# 5411507.net
KiCad netlist of a schematic drawn in EAGLE
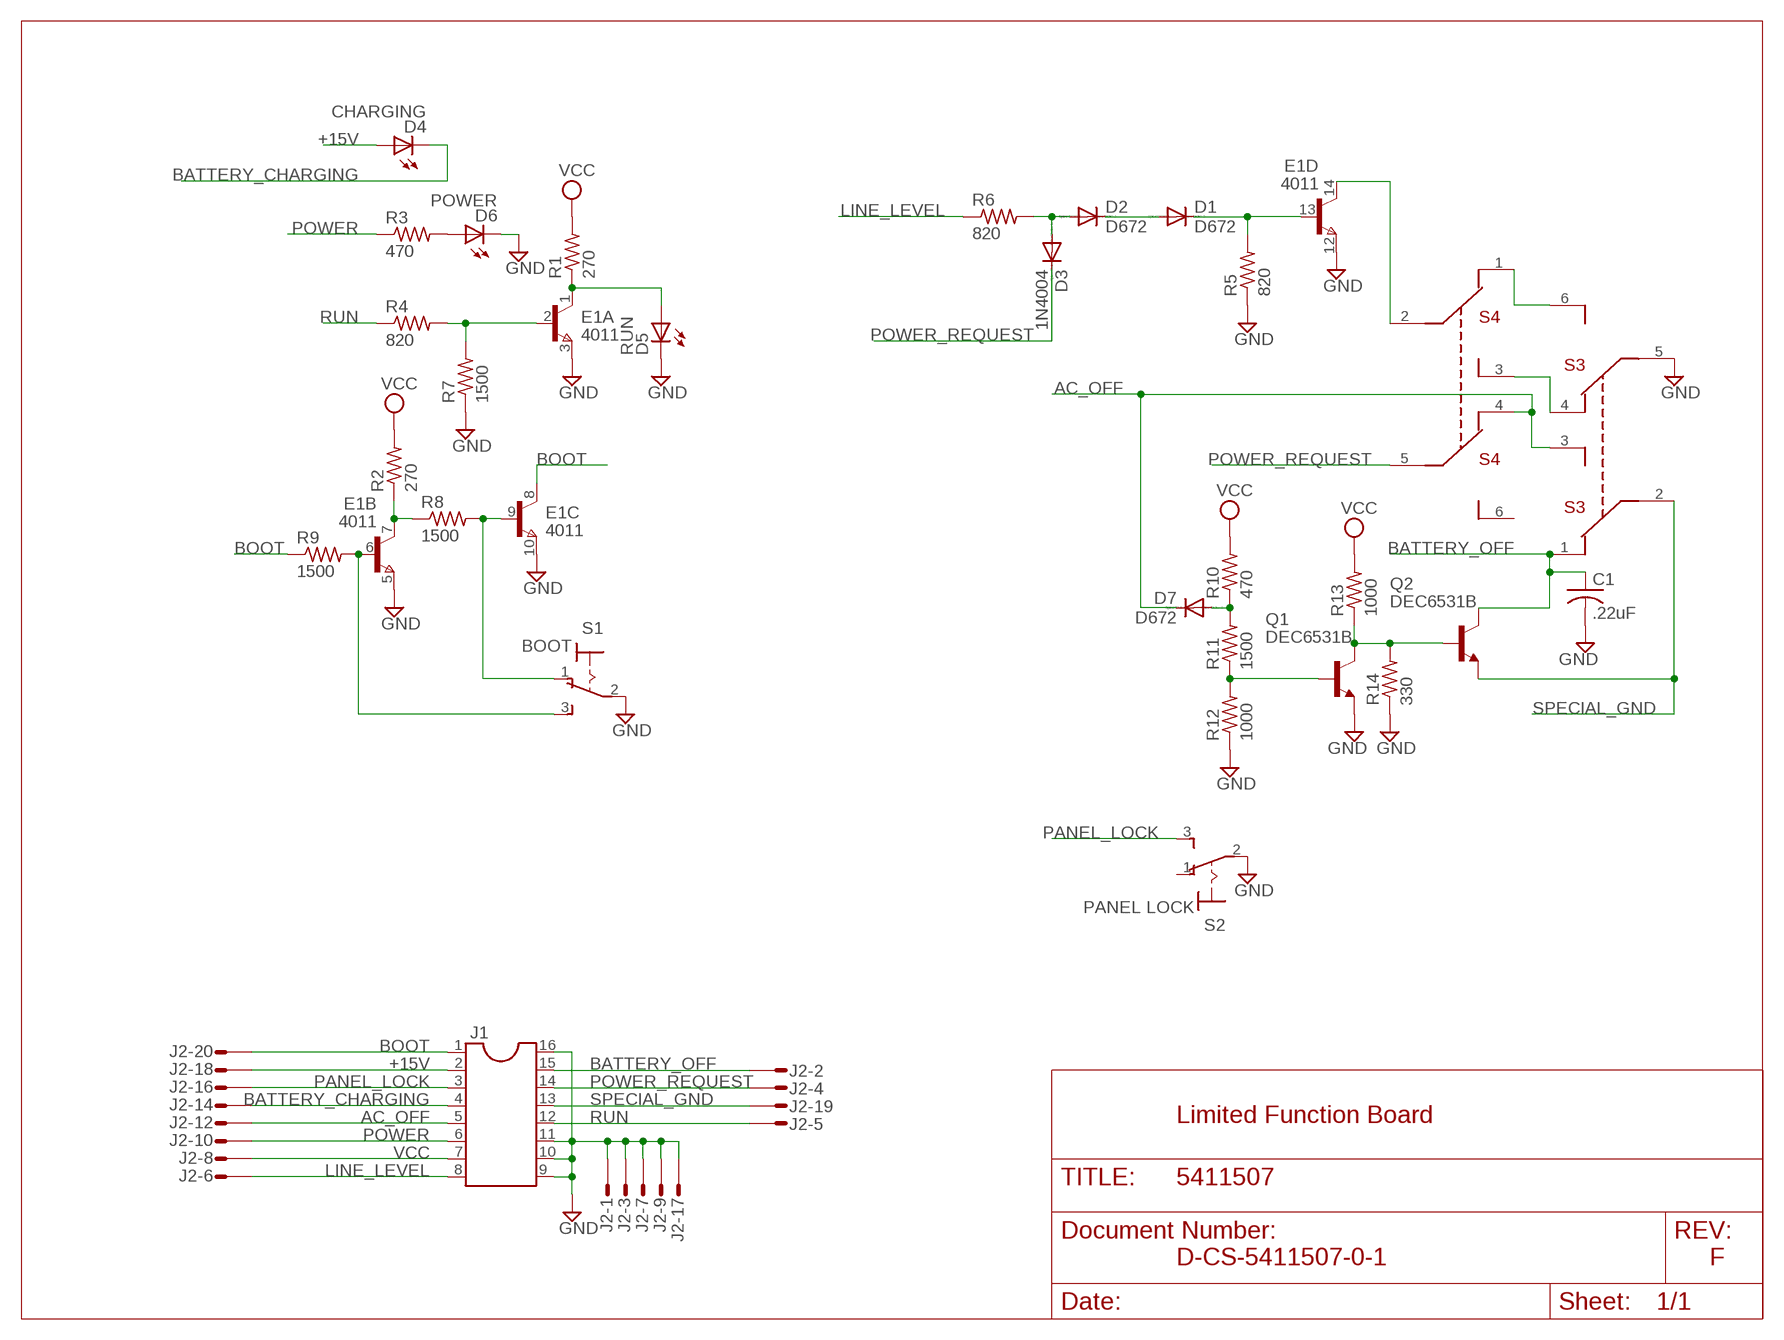
[diagram p0: schematic, sheet 1]

(export (version "E")
  (design (tool "Eeschema 10.0.6"))
  (components
    (comp (ref "C1")
      (value ".22uF")
      (footprint "eagle-import:C050-030X075")
      (libsource (lib "eagle-import") (part "C-US050-030X075"))
    )
    (comp (ref "D1")
      (value "D672")
      (footprint "eagle-import:DO35-10")
      (libsource (lib "eagle-import") (part "DIODE-DO35-10"))
    )
    (comp (ref "D2")
      (value "D672")
      (footprint "eagle-import:DO35-10")
      (libsource (lib "eagle-import") (part "DIODE-DO35-10"))
    )
    (comp (ref "D3")
      (value "1N4004")
      (footprint "eagle-import:DO41-10")
      (libsource (lib "eagle-import") (part "1N4004"))
    )
    (comp (ref "D4")
      (value "CHARGING")
      (footprint "eagle-import:LED5MM")
      (libsource (lib "eagle-import") (part "LED5MM"))
    )
    (comp (ref "D5")
      (value "RUN")
      (footprint "eagle-import:LED5MM")
      (libsource (lib "eagle-import") (part "LED5MM"))
    )
    (comp (ref "D6")
      (value "POWER")
      (footprint "eagle-import:LED5MM")
      (libsource (lib "eagle-import") (part "LED5MM"))
    )
    (comp (ref "D7")
      (value "D672")
      (footprint "eagle-import:DO35-10")
      (libsource (lib "eagle-import") (part "DIODE-DO35-10"))
    )
    (comp (ref "E1")
      (value "4011")
      (footprint "eagle-import:DIL14")
      (libsource (lib "eagle-import") (part "MAT-04Y"))
    )
    (comp (ref "J1")
      (value "DIL16S")
      (footprint "eagle-import:SOCKET-16")
      (libsource (lib "eagle-import") (part "DIL16S"))
    )
    (comp (ref "J2")
      (value "20HS")
      (footprint "eagle-import:20H")
      (libsource (lib "eagle-import") (part "20HS"))
    )
    (comp (ref "Q1")
      (value "DEC6531B")
      (footprint "eagle-import:TO5")
      (libsource (lib "eagle-import") (part "-NPN-TO5"))
    )
    (comp (ref "Q2")
      (value "DEC6531B")
      (footprint "eagle-import:TO5")
      (libsource (lib "eagle-import") (part "-NPN-TO5"))
    )
    (comp (ref "R1")
      (value "270")
      (footprint "eagle-import:0207_10")
      (libsource (lib "eagle-import") (part "R-US_0207/10"))
    )
    (comp (ref "R2")
      (value "270")
      (footprint "eagle-import:0207_10")
      (libsource (lib "eagle-import") (part "R-US_0207/10"))
    )
    (comp (ref "R3")
      (value "470")
      (footprint "eagle-import:0207_10")
      (libsource (lib "eagle-import") (part "R-US_0207/10"))
    )
    (comp (ref "R4")
      (value "820")
      (footprint "eagle-import:0207_10")
      (libsource (lib "eagle-import") (part "R-US_0207/10"))
    )
    (comp (ref "R5")
      (value "820")
      (footprint "eagle-import:0207_10")
      (libsource (lib "eagle-import") (part "R-US_0207/10"))
    )
    (comp (ref "R6")
      (value "820")
      (footprint "eagle-import:0207_10")
      (libsource (lib "eagle-import") (part "R-US_0207/10"))
    )
    (comp (ref "R7")
      (value "1500")
      (footprint "eagle-import:0207_10")
      (libsource (lib "eagle-import") (part "R-US_0207/10"))
    )
    (comp (ref "R8")
      (value "1500")
      (footprint "eagle-import:0207_10")
      (libsource (lib "eagle-import") (part "R-US_0207/10"))
    )
    (comp (ref "R9")
      (value "1500")
      (footprint "eagle-import:0207_10")
      (libsource (lib "eagle-import") (part "R-US_0207/10"))
    )
    (comp (ref "R10")
      (value "470")
      (footprint "eagle-import:0207_10")
      (libsource (lib "eagle-import") (part "R-US_0207/10"))
    )
    (comp (ref "R11")
      (value "1500")
      (footprint "eagle-import:0207_10")
      (libsource (lib "eagle-import") (part "R-US_0207/10"))
    )
    (comp (ref "R12")
      (value "1000")
      (footprint "eagle-import:0207_10")
      (libsource (lib "eagle-import") (part "R-US_0207/10"))
    )
    (comp (ref "R13")
      (value "1000")
      (footprint "eagle-import:0207_10")
      (libsource (lib "eagle-import") (part "R-US_0207/10"))
    )
    (comp (ref "R14")
      (value "330")
      (footprint "eagle-import:0207_10")
      (libsource (lib "eagle-import") (part "R-US_0207/10"))
    )
    (comp (ref "S1")
      (value "BOOT")
      (footprint "eagle-import:7109MD9V3")
      (libsource (lib "eagle-import") (part "710X"))
    )
    (comp (ref "S2")
      (value "PANEL LOCK")
      (footprint "eagle-import:7109MD9V3")
      (libsource (lib "eagle-import") (part "710X"))
    )
    (comp (ref "S3")
      (value "ON/OFF")
      (footprint "eagle-import:7209MD9V3")
      (libsource (lib "eagle-import") (part "720X"))
    )
    (comp (ref "S4")
      (value "M/S")
      (footprint "eagle-import:7209MD9V3")
      (libsource (lib "eagle-import") (part "720X"))
    )
  )
  (nets
    (net (code "1") (name "/+15V") (class "Default")
      (node (ref "D4") (pin "A") (pinfunction "A_A") (pintype "passive"))
      (node (ref "J1") (pin "2") (pinfunction "2_2") (pintype "passive"))
      (node (ref "J2") (pin "18") (pinfunction "S_18") (pintype "passive"))
    )
    (net (code "2") (name "/AC_OFF") (class "Default")
      (node (ref "D7") (pin "C") (pinfunction "C_C") (pintype "passive"))
      (node (ref "J1") (pin "5") (pinfunction "5_5") (pintype "passive"))
      (node (ref "J2") (pin "12") (pinfunction "S_12") (pintype "passive"))
      (node (ref "S3") (pin "3") (pinfunction "A3_3") (pintype "bidirectional"))
      (node (ref "S4") (pin "4") (pinfunction "B1_4") (pintype "bidirectional"))
    )
    (net (code "3") (name "/BATTERY_CHARGING") (class "Default")
      (node (ref "D4") (pin "K") (pinfunction "C_K") (pintype "passive"))
      (node (ref "J1") (pin "4") (pinfunction "4_4") (pintype "passive"))
      (node (ref "J2") (pin "14") (pinfunction "S_14") (pintype "passive"))
    )
    (net (code "4") (name "/BATTERY_OFF") (class "Default")
      (node (ref "C1") (pin "1") (pinfunction "1_1") (pintype "passive"))
      (node (ref "J1") (pin "15") (pinfunction "15_15") (pintype "passive"))
      (node (ref "J2") (pin "2") (pinfunction "S_2") (pintype "passive"))
      (node (ref "Q2") (pin "3") (pinfunction "C_3") (pintype "passive"))
      (node (ref "S3") (pin "1") (pinfunction "A1_1") (pintype "bidirectional"))
    )
    (net (code "5") (name "/BOOT") (class "Default")
      (node (ref "E1") (pin "8") (pinfunction "C_8") (pintype "passive"))
      (node (ref "J1") (pin "1") (pinfunction "1_1") (pintype "passive"))
      (node (ref "J2") (pin "20") (pinfunction "S_20") (pintype "passive"))
      (node (ref "R9") (pin "1") (pinfunction "1_1") (pintype "passive"))
    )
    (net (code "6") (name "/LINE_LEVEL") (class "Default")
      (node (ref "J1") (pin "8") (pinfunction "8_8") (pintype "passive"))
      (node (ref "J2") (pin "6") (pinfunction "S_6") (pintype "passive"))
      (node (ref "R6") (pin "1") (pinfunction "1_1") (pintype "passive"))
    )
    (net (code "7") (name "/PANEL_LOCK") (class "Default")
      (node (ref "J1") (pin "3") (pinfunction "3_3") (pintype "passive"))
      (node (ref "J2") (pin "16") (pinfunction "S_16") (pintype "passive"))
      (node (ref "S2") (pin "3") (pinfunction "S_3") (pintype "passive"))
    )
    (net (code "8") (name "/POWER") (class "Default")
      (node (ref "J1") (pin "6") (pinfunction "6_6") (pintype "passive"))
      (node (ref "J2") (pin "10") (pinfunction "S_10") (pintype "passive"))
      (node (ref "R3") (pin "1") (pinfunction "1_1") (pintype "passive"))
    )
    (net (code "9") (name "/POWER_REQUEST") (class "Default")
      (node (ref "D3") (pin "C") (pinfunction "C_C") (pintype "passive"))
      (node (ref "J1") (pin "14") (pinfunction "14_14") (pintype "passive"))
      (node (ref "J2") (pin "4") (pinfunction "S_4") (pintype "passive"))
      (node (ref "S4") (pin "5") (pinfunction "B2_5") (pintype "bidirectional"))
    )
    (net (code "10") (name "/RUN") (class "Default")
      (node (ref "J1") (pin "12") (pinfunction "12_12") (pintype "passive"))
      (node (ref "J2") (pin "5") (pinfunction "S_5") (pintype "passive"))
      (node (ref "R4") (pin "1") (pinfunction "1_1") (pintype "passive"))
    )
    (net (code "11") (name "/SPECIAL_GND") (class "Default")
      (node (ref "J1") (pin "13") (pinfunction "13_13") (pintype "passive"))
      (node (ref "J2") (pin "19") (pinfunction "S_19") (pintype "passive"))
      (node (ref "Q2") (pin "1") (pinfunction "E_1") (pintype "passive"))
      (node (ref "S3") (pin "2") (pinfunction "A2_2") (pintype "bidirectional"))
    )
    (net (code "12") (name "GND") (class "Default")
      (node (ref "C1") (pin "2") (pinfunction "2_2") (pintype "passive"))
      (node (ref "D5") (pin "K") (pinfunction "C_K") (pintype "passive"))
      (node (ref "D6") (pin "K") (pinfunction "C_K") (pintype "passive"))
      (node (ref "E1") (pin "10") (pinfunction "E_10") (pintype "passive"))
      (node (ref "E1") (pin "12") (pinfunction "E_12") (pintype "passive"))
      (node (ref "E1") (pin "3") (pinfunction "E_3") (pintype "passive"))
      (node (ref "E1") (pin "5") (pinfunction "E_5") (pintype "passive"))
      (node (ref "J1") (pin "10") (pinfunction "10_10") (pintype "passive"))
      (node (ref "J1") (pin "11") (pinfunction "11_11") (pintype "passive"))
      (node (ref "J1") (pin "16") (pinfunction "16_16") (pintype "passive"))
      (node (ref "J1") (pin "9") (pinfunction "9_9") (pintype "passive"))
      (node (ref "J2") (pin "1") (pinfunction "S_1") (pintype "passive"))
      (node (ref "J2") (pin "17") (pinfunction "S_17") (pintype "passive"))
      (node (ref "J2") (pin "3") (pinfunction "S_3") (pintype "passive"))
      (node (ref "J2") (pin "7") (pinfunction "S_7") (pintype "passive"))
      (node (ref "J2") (pin "9") (pinfunction "S_9") (pintype "passive"))
      (node (ref "Q1") (pin "1") (pinfunction "E_1") (pintype "passive"))
      (node (ref "R12") (pin "1") (pinfunction "1_1") (pintype "passive"))
      (node (ref "R14") (pin "1") (pinfunction "1_1") (pintype "passive"))
      (node (ref "R5") (pin "1") (pinfunction "1_1") (pintype "passive"))
      (node (ref "R7") (pin "1") (pinfunction "1_1") (pintype "passive"))
      (node (ref "S1") (pin "2") (pinfunction "P_2") (pintype "passive"))
      (node (ref "S2") (pin "2") (pinfunction "P_2") (pintype "passive"))
      (node (ref "S3") (pin "5") (pinfunction "B2_5") (pintype "bidirectional"))
    )
    (net (code "13") (name "Net-(D1-PadA)") (class "Default")
      (node (ref "D1") (pin "A") (pinfunction "A_A") (pintype "passive"))
      (node (ref "D2") (pin "C") (pinfunction "C_C") (pintype "passive"))
    )
    (net (code "14") (name "Net-(D2-PadA)") (class "Default")
      (node (ref "D2") (pin "A") (pinfunction "A_A") (pintype "passive"))
      (node (ref "D3") (pin "A") (pinfunction "A_A") (pintype "passive"))
      (node (ref "R6") (pin "2") (pinfunction "2_2") (pintype "passive"))
    )
    (net (code "15") (name "Net-(D6-PadA)") (class "Default")
      (node (ref "D6") (pin "A") (pinfunction "A_A") (pintype "passive"))
      (node (ref "R3") (pin "2") (pinfunction "2_2") (pintype "passive"))
    )
    (net (code "16") (name "Net-(D7-PadA)") (class "Default")
      (node (ref "D7") (pin "A") (pinfunction "A_A") (pintype "passive"))
      (node (ref "R10") (pin "1") (pinfunction "1_1") (pintype "passive"))
      (node (ref "R11") (pin "2") (pinfunction "2_2") (pintype "passive"))
    )
    (net (code "17") (name "Net-(E1A-B)") (class "Default")
      (node (ref "E1") (pin "2") (pinfunction "B_2") (pintype "passive"))
      (node (ref "R4") (pin "2") (pinfunction "2_2") (pintype "passive"))
      (node (ref "R7") (pin "2") (pinfunction "2_2") (pintype "passive"))
    )
    (net (code "18") (name "Net-(E1A-C)") (class "Default")
      (node (ref "D5") (pin "A") (pinfunction "A_A") (pintype "passive"))
      (node (ref "E1") (pin "1") (pinfunction "C_1") (pintype "passive"))
      (node (ref "R1") (pin "1") (pinfunction "1_1") (pintype "passive"))
    )
    (net (code "19") (name "Net-(E1B-B)") (class "Default")
      (node (ref "E1") (pin "6") (pinfunction "B_6") (pintype "passive"))
      (node (ref "R9") (pin "2") (pinfunction "2_2") (pintype "passive"))
      (node (ref "S1") (pin "3") (pinfunction "S_3") (pintype "passive"))
    )
    (net (code "20") (name "Net-(E1B-C)") (class "Default")
      (node (ref "E1") (pin "7") (pinfunction "C_7") (pintype "passive"))
      (node (ref "R2") (pin "1") (pinfunction "1_1") (pintype "passive"))
      (node (ref "R8") (pin "1") (pinfunction "1_1") (pintype "passive"))
    )
    (net (code "21") (name "Net-(E1C-B)") (class "Default")
      (node (ref "E1") (pin "9") (pinfunction "B_9") (pintype "passive"))
      (node (ref "R8") (pin "2") (pinfunction "2_2") (pintype "passive"))
      (node (ref "S1") (pin "1") (pinfunction "O_1") (pintype "passive"))
    )
    (net (code "22") (name "Net-(E1D-B)") (class "Default")
      (node (ref "D1") (pin "C") (pinfunction "C_C") (pintype "passive"))
      (node (ref "E1") (pin "13") (pinfunction "B_13") (pintype "passive"))
      (node (ref "R5") (pin "2") (pinfunction "2_2") (pintype "passive"))
    )
    (net (code "23") (name "Net-(E1D-C)") (class "Default")
      (node (ref "E1") (pin "14") (pinfunction "C_14") (pintype "passive"))
      (node (ref "S4") (pin "2") (pinfunction "A2_2") (pintype "bidirectional"))
    )
    (net (code "24") (name "Net-(Q1-B)") (class "Default")
      (node (ref "Q1") (pin "2") (pinfunction "B_2") (pintype "passive"))
      (node (ref "R11") (pin "1") (pinfunction "1_1") (pintype "passive"))
      (node (ref "R12") (pin "2") (pinfunction "2_2") (pintype "passive"))
    )
    (net (code "25") (name "Net-(Q1-C)") (class "Default")
      (node (ref "Q1") (pin "3") (pinfunction "C_3") (pintype "passive"))
      (node (ref "Q2") (pin "2") (pinfunction "B_2") (pintype "passive"))
      (node (ref "R13") (pin "1") (pinfunction "1_1") (pintype "passive"))
      (node (ref "R14") (pin "2") (pinfunction "2_2") (pintype "passive"))
    )
    (net (code "26") (name "Net-(S3A-B1)") (class "Default")
      (node (ref "S3") (pin "4") (pinfunction "B1_4") (pintype "bidirectional"))
      (node (ref "S4") (pin "3") (pinfunction "A3_3") (pintype "bidirectional"))
    )
    (net (code "27") (name "Net-(S3A-B3)") (class "Default")
      (node (ref "S3") (pin "6") (pinfunction "B3_6") (pintype "bidirectional"))
      (node (ref "S4") (pin "1") (pinfunction "A1_1") (pintype "bidirectional"))
    )
    (net (code "28") (name "VCC") (class "Default")
      (node (ref "J1") (pin "7") (pinfunction "7_7") (pintype "passive"))
      (node (ref "J2") (pin "8") (pinfunction "S_8") (pintype "passive"))
      (node (ref "R1") (pin "2") (pinfunction "2_2") (pintype "passive"))
      (node (ref "R10") (pin "2") (pinfunction "2_2") (pintype "passive"))
      (node (ref "R13") (pin "2") (pinfunction "2_2") (pintype "passive"))
      (node (ref "R2") (pin "2") (pinfunction "2_2") (pintype "passive"))
    )
    (net (code "29") (name "unconnected-(S2A-O-Pad1)") (class "Default")
      (node (ref "S2") (pin "1") (pinfunction "O_1") (pintype "passive"))
    )
    (net (code "30") (name "unconnected-(S4A-B3-Pad6)") (class "Default")
      (node (ref "S4") (pin "6") (pinfunction "B3_6") (pintype "bidirectional"))
    )
  )
)
